# OpenSegment-v10.net
KiCad netlist of a schematic drawn in EAGLE
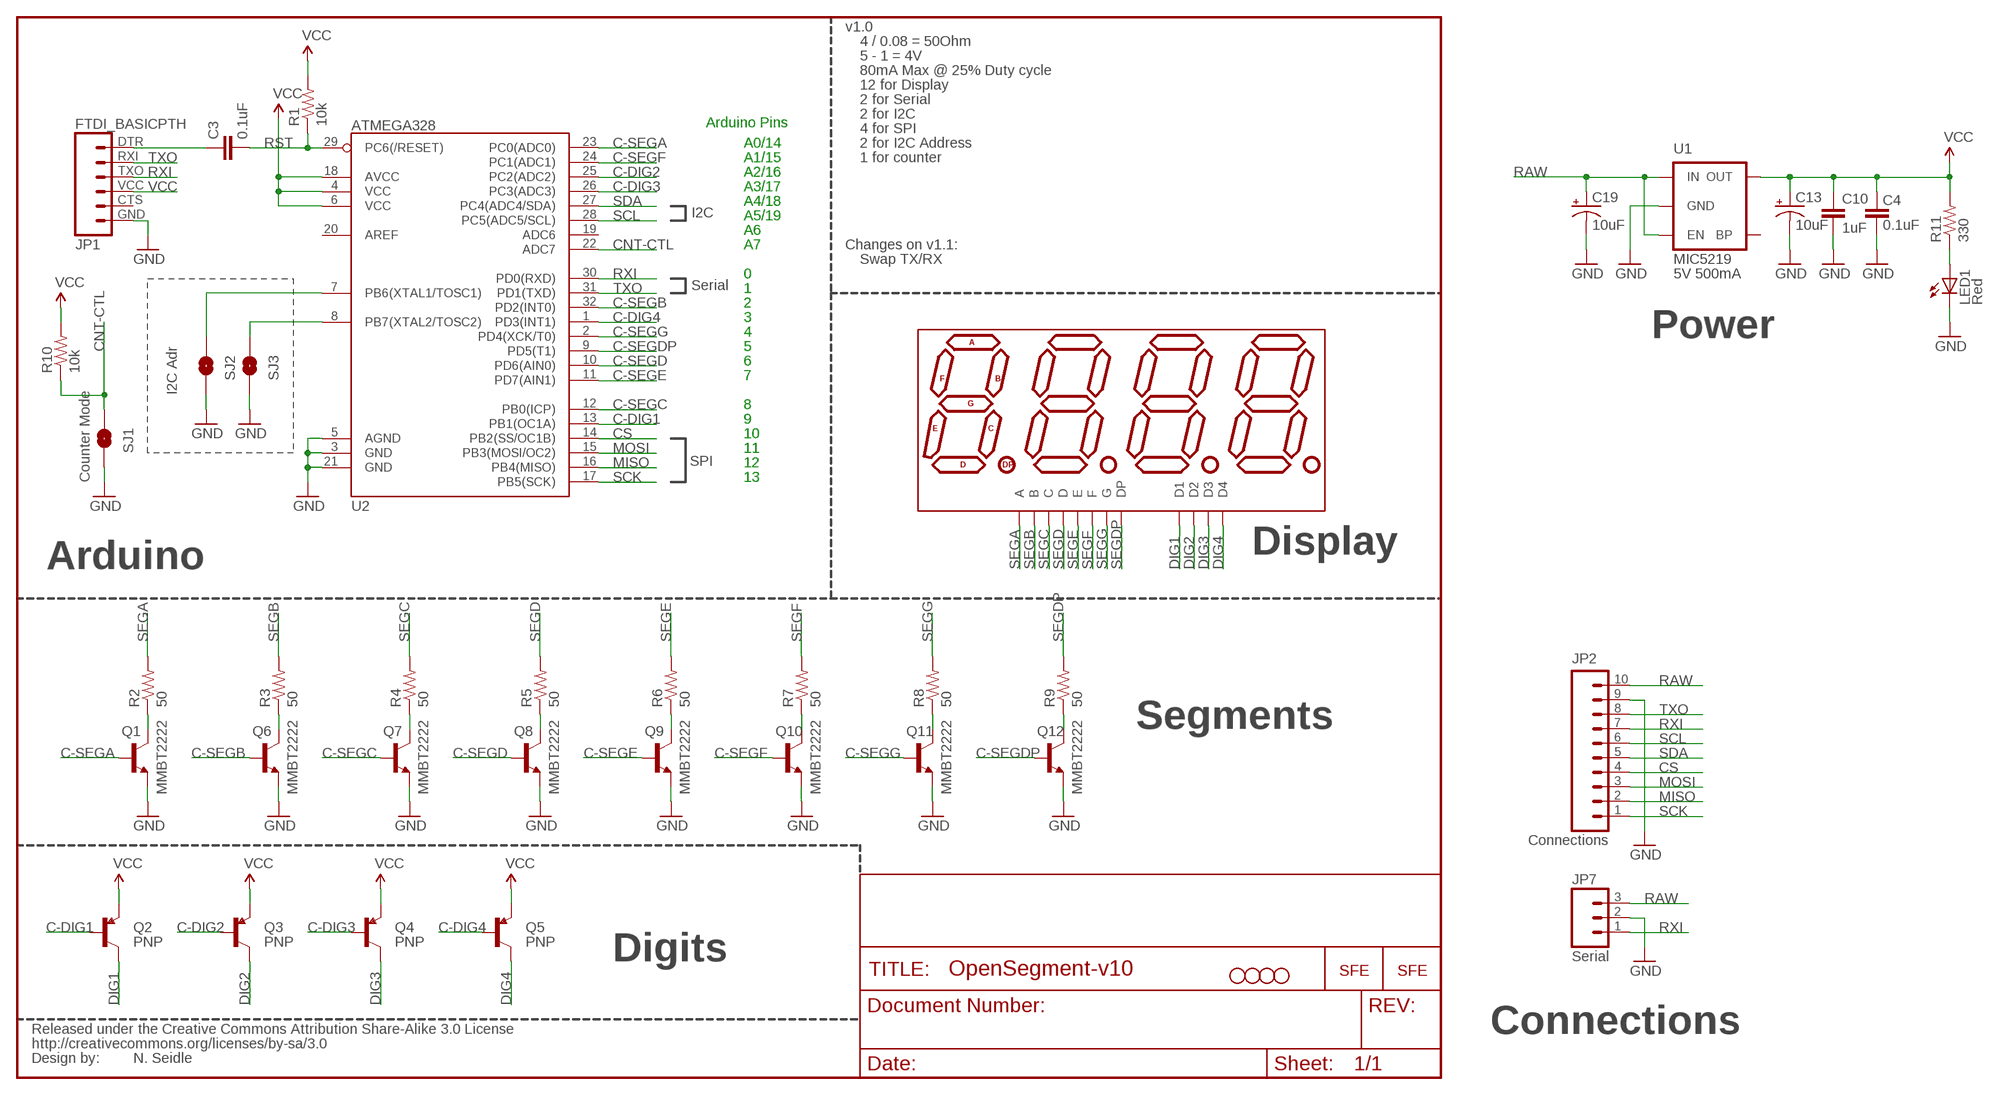
[diagram p0: schematic, sheet 1]

(export (version "E")
  (design (tool "Eeschema 10.0.6"))
  (components
    (comp (ref "C3")
      (value "0.1uF")
      (footprint "eagle-import:0402-CAP")
      (libsource (lib "eagle-import") (part "CAP0402-CAP"))
    )
    (comp (ref "C4")
      (value "0.1uF")
      (footprint "eagle-import:0402-CAP")
      (libsource (lib "eagle-import") (part "CAP0402-CAP"))
    )
    (comp (ref "C10")
      (value "1uF")
      (footprint "eagle-import:0402-CAP")
      (libsource (lib "eagle-import") (part "CAP0402-CAP"))
    )
    (comp (ref "C13")
      (value "10uF")
      (footprint "eagle-import:EIA3216")
      (libsource (lib "eagle-import") (part "CAP_POL1206"))
    )
    (comp (ref "C19")
      (value "10uF")
      (footprint "eagle-import:EIA3216")
      (libsource (lib "eagle-import") (part "CAP_POL1206"))
    )
    (comp (ref "JP1")
      (value "FTDI_BASICPTH")
      (footprint "eagle-import:FTDI_BASIC")
      (libsource (lib "eagle-import") (part "FTDI_BASICPTH"))
    )
    (comp (ref "JP2")
      (value "Connections")
      (footprint "eagle-import:1X10")
      (libsource (lib "eagle-import") (part "M10{dblquote}"))
    )
    (comp (ref "JP3")
      (value "STAND-OFF")
      (footprint "eagle-import:STAND-OFF")
      (libsource (lib "eagle-import") (part "STAND-OFF"))
    )
    (comp (ref "JP4")
      (value "STAND-OFF")
      (footprint "eagle-import:STAND-OFF")
      (libsource (lib "eagle-import") (part "STAND-OFF"))
    )
    (comp (ref "JP5")
      (value "STAND-OFF")
      (footprint "eagle-import:STAND-OFF")
      (libsource (lib "eagle-import") (part "STAND-OFF"))
    )
    (comp (ref "JP6")
      (value "STAND-OFF")
      (footprint "eagle-import:STAND-OFF")
      (libsource (lib "eagle-import") (part "STAND-OFF"))
    )
    (comp (ref "JP7")
      (value "Serial")
      (footprint "eagle-import:JST-3-SMD")
      (libsource (lib "eagle-import") (part "M03"))
    )
    (comp (ref "LED1")
      (value "Red")
      (footprint "eagle-import:LED-0603")
      (libsource (lib "eagle-import") (part "LED0603"))
    )
    (comp (ref "Q1")
      (value "MMBT2222")
      (footprint "eagle-import:SOT23-3")
      (libsource (lib "eagle-import") (part "TRANSISTOR_NPNSOT23-3"))
    )
    (comp (ref "Q2")
      (value "PNP")
      (footprint "eagle-import:SOT23-3")
      (libsource (lib "eagle-import") (part "TRANSISTOR_PNPSMD"))
    )
    (comp (ref "Q3")
      (value "PNP")
      (footprint "eagle-import:SOT23-3")
      (libsource (lib "eagle-import") (part "TRANSISTOR_PNPSMD"))
    )
    (comp (ref "Q4")
      (value "PNP")
      (footprint "eagle-import:SOT23-3")
      (libsource (lib "eagle-import") (part "TRANSISTOR_PNPSMD"))
    )
    (comp (ref "Q5")
      (value "PNP")
      (footprint "eagle-import:SOT23-3")
      (libsource (lib "eagle-import") (part "TRANSISTOR_PNPSMD"))
    )
    (comp (ref "Q6")
      (value "MMBT2222")
      (footprint "eagle-import:SOT23-3")
      (libsource (lib "eagle-import") (part "TRANSISTOR_NPNSOT23-3"))
    )
    (comp (ref "Q7")
      (value "MMBT2222")
      (footprint "eagle-import:SOT23-3")
      (libsource (lib "eagle-import") (part "TRANSISTOR_NPNSOT23-3"))
    )
    (comp (ref "Q8")
      (value "MMBT2222")
      (footprint "eagle-import:SOT23-3")
      (libsource (lib "eagle-import") (part "TRANSISTOR_NPNSOT23-3"))
    )
    (comp (ref "Q9")
      (value "MMBT2222")
      (footprint "eagle-import:SOT23-3")
      (libsource (lib "eagle-import") (part "TRANSISTOR_NPNSOT23-3"))
    )
    (comp (ref "Q10")
      (value "MMBT2222")
      (footprint "eagle-import:SOT23-3")
      (libsource (lib "eagle-import") (part "TRANSISTOR_NPNSOT23-3"))
    )
    (comp (ref "Q11")
      (value "MMBT2222")
      (footprint "eagle-import:SOT23-3")
      (libsource (lib "eagle-import") (part "TRANSISTOR_NPNSOT23-3"))
    )
    (comp (ref "Q12")
      (value "MMBT2222")
      (footprint "eagle-import:SOT23-3")
      (libsource (lib "eagle-import") (part "TRANSISTOR_NPNSOT23-3"))
    )
    (comp (ref "R1")
      (value "10k")
      (footprint "eagle-import:0402-RES")
      (libsource (lib "eagle-import") (part "RESISTOR0402-RES"))
    )
    (comp (ref "R2")
      (value "50")
      (footprint "eagle-import:0402-RES")
      (libsource (lib "eagle-import") (part "RESISTOR0402-RES"))
    )
    (comp (ref "R3")
      (value "50")
      (footprint "eagle-import:0402-RES")
      (libsource (lib "eagle-import") (part "RESISTOR0402-RES"))
    )
    (comp (ref "R4")
      (value "50")
      (footprint "eagle-import:0402-RES")
      (libsource (lib "eagle-import") (part "RESISTOR0402-RES"))
    )
    (comp (ref "R5")
      (value "50")
      (footprint "eagle-import:0402-RES")
      (libsource (lib "eagle-import") (part "RESISTOR0402-RES"))
    )
    (comp (ref "R6")
      (value "50")
      (footprint "eagle-import:0402-RES")
      (libsource (lib "eagle-import") (part "RESISTOR0402-RES"))
    )
    (comp (ref "R7")
      (value "50")
      (footprint "eagle-import:0402-RES")
      (libsource (lib "eagle-import") (part "RESISTOR0402-RES"))
    )
    (comp (ref "R8")
      (value "50")
      (footprint "eagle-import:0402-RES")
      (libsource (lib "eagle-import") (part "RESISTOR0402-RES"))
    )
    (comp (ref "R9")
      (value "50")
      (footprint "eagle-import:0402-RES")
      (libsource (lib "eagle-import") (part "RESISTOR0402-RES"))
    )
    (comp (ref "R10")
      (value "10k")
      (footprint "eagle-import:0402-RES")
      (libsource (lib "eagle-import") (part "RESISTOR0402-RES"))
    )
    (comp (ref "R11")
      (value "330")
      (footprint "eagle-import:0402-RES")
      (libsource (lib "eagle-import") (part "RESISTOR0402-RES"))
    )
    (comp (ref "SJ1")
      (value "Counter Ctl")
      (footprint "eagle-import:SJ_2S-NO")
      (libsource (lib "eagle-import") (part "SOLDERJUMPERNO"))
    )
    (comp (ref "SJ2")
      (value "Counter Ctl")
      (footprint "eagle-import:SJ_2S-NO")
      (libsource (lib "eagle-import") (part "SOLDERJUMPERNO"))
    )
    (comp (ref "SJ3")
      (value "Counter Ctl")
      (footprint "eagle-import:SJ_2S-NO")
      (libsource (lib "eagle-import") (part "SOLDERJUMPERNO"))
    )
    (comp (ref "U$1")
      (value "LOGO-SFESK")
      (footprint "eagle-import:SFE-LOGO-FLAME")
      (libsource (lib "eagle-import") (part "LOGO-SFESK"))
    )
    (comp (ref "U$3")
      (value "CREATIVE_COMMONS")
      (footprint "eagle-import:CREATIVE_COMMONS")
      (libsource (lib "eagle-import") (part "CREATIVE_COMMONS"))
    )
    (comp (ref "U$7")
      (value "LOGO-SFENW2")
      (footprint "eagle-import:SFE-NEW-WEB")
      (libsource (lib "eagle-import") (part "LOGO-SFENW2"))
    )
    (comp (ref "U1")
      (value "MIC5219")
      (footprint "eagle-import:SOT23-5")
      (libsource (lib "eagle-import") (part "V_REG_LDOSMD"))
    )
    (comp (ref "U2")
      (value "ATMEGA328")
      (footprint "eagle-import:TQFP32-08")
      (libsource (lib "eagle-import") (part "ATMEGA168"))
    )
    (comp (ref "U3")
      (value "7-SEGMENT-4DIGIT-COUNTERPTH")
      (footprint "eagle-import:7-SEGMENT-4DIGIT-COUNTER")
      (libsource (lib "eagle-import") (part "7-SEGMENT-4DIGIT-COUNTERPTH"))
    )
  )
  (nets
    (net (code "1") (name "/C-DIG1") (class "Default")
      (node (ref "Q2") (pin "1") (pinfunction "B_1") (pintype "passive"))
      (node (ref "U2") (pin "13") (pinfunction "PB1(OC1A)_13") (pintype "bidirectional"))
    )
    (net (code "2") (name "/C-DIG2") (class "Default")
      (node (ref "Q3") (pin "1") (pinfunction "B_1") (pintype "passive"))
      (node (ref "U2") (pin "25") (pinfunction "PC2(ADC2)_25") (pintype "bidirectional"))
    )
    (net (code "3") (name "/C-DIG3") (class "Default")
      (node (ref "Q4") (pin "1") (pinfunction "B_1") (pintype "passive"))
      (node (ref "U2") (pin "26") (pinfunction "PC3(ADC3)_26") (pintype "bidirectional"))
    )
    (net (code "4") (name "/C-DIG4") (class "Default")
      (node (ref "Q5") (pin "1") (pinfunction "B_1") (pintype "passive"))
      (node (ref "U2") (pin "1") (pinfunction "PD3(INT1)_1") (pintype "bidirectional"))
    )
    (net (code "5") (name "/C-SEGA") (class "Default")
      (node (ref "Q1") (pin "1") (pinfunction "B_1") (pintype "passive"))
      (node (ref "U2") (pin "23") (pinfunction "PC0(ADC0)_23") (pintype "bidirectional"))
    )
    (net (code "6") (name "/C-SEGB") (class "Default")
      (node (ref "Q6") (pin "1") (pinfunction "B_1") (pintype "passive"))
      (node (ref "U2") (pin "32") (pinfunction "PD2(INT0)_32") (pintype "bidirectional"))
    )
    (net (code "7") (name "/C-SEGC") (class "Default")
      (node (ref "Q7") (pin "1") (pinfunction "B_1") (pintype "passive"))
      (node (ref "U2") (pin "12") (pinfunction "PB0(ICP)_12") (pintype "bidirectional"))
    )
    (net (code "8") (name "/C-SEGD") (class "Default")
      (node (ref "Q8") (pin "1") (pinfunction "B_1") (pintype "passive"))
      (node (ref "U2") (pin "10") (pinfunction "PD6(AIN0)_10") (pintype "bidirectional"))
    )
    (net (code "9") (name "/C-SEGDP") (class "Default")
      (node (ref "Q12") (pin "1") (pinfunction "B_1") (pintype "passive"))
      (node (ref "U2") (pin "9") (pinfunction "PD5(T1)_9") (pintype "bidirectional"))
    )
    (net (code "10") (name "/C-SEGE") (class "Default")
      (node (ref "Q9") (pin "1") (pinfunction "B_1") (pintype "passive"))
      (node (ref "U2") (pin "11") (pinfunction "PD7(AIN1)_11") (pintype "bidirectional"))
    )
    (net (code "11") (name "/C-SEGF") (class "Default")
      (node (ref "Q10") (pin "1") (pinfunction "B_1") (pintype "passive"))
      (node (ref "U2") (pin "24") (pinfunction "PC1(ADC1)_24") (pintype "bidirectional"))
    )
    (net (code "12") (name "/C-SEGG") (class "Default")
      (node (ref "Q11") (pin "1") (pinfunction "B_1") (pintype "passive"))
      (node (ref "U2") (pin "2") (pinfunction "PD4(XCK/T0)_2") (pintype "bidirectional"))
    )
    (net (code "13") (name "/CNT-CTL") (class "Default")
      (node (ref "R10") (pin "1") (pinfunction "1_1") (pintype "passive"))
      (node (ref "SJ1") (pin "1") (pinfunction "1_1") (pintype "passive"))
      (node (ref "U2") (pin "22") (pinfunction "ADC7_22") (pintype "bidirectional"))
    )
    (net (code "14") (name "/CS") (class "Default")
      (node (ref "JP2") (pin "4") (pinfunction "4_4") (pintype "passive"))
      (node (ref "U2") (pin "14") (pinfunction "PB2(SS/OC1B)_14") (pintype "bidirectional"))
    )
    (net (code "15") (name "/DIG1") (class "Default")
      (node (ref "Q2") (pin "3") (pinfunction "C_3") (pintype "passive"))
      (node (ref "U3") (pin "12") (pinfunction "D1_12") (pintype "bidirectional"))
    )
    (net (code "16") (name "/DIG2") (class "Default")
      (node (ref "Q3") (pin "3") (pinfunction "C_3") (pintype "passive"))
      (node (ref "U3") (pin "9") (pinfunction "D2_9") (pintype "bidirectional"))
    )
    (net (code "17") (name "/DIG3") (class "Default")
      (node (ref "Q4") (pin "3") (pinfunction "C_3") (pintype "passive"))
      (node (ref "U3") (pin "8") (pinfunction "D3_8") (pintype "bidirectional"))
    )
    (net (code "18") (name "/DIG4") (class "Default")
      (node (ref "Q5") (pin "3") (pinfunction "C_3") (pintype "passive"))
      (node (ref "U3") (pin "6") (pinfunction "D4_6") (pintype "bidirectional"))
    )
    (net (code "19") (name "/MISO") (class "Default")
      (node (ref "JP2") (pin "2") (pinfunction "2_2") (pintype "passive"))
      (node (ref "U2") (pin "16") (pinfunction "PB4(MISO)_16") (pintype "bidirectional"))
    )
    (net (code "20") (name "/MOSI") (class "Default")
      (node (ref "JP2") (pin "3") (pinfunction "3_3") (pintype "passive"))
      (node (ref "U2") (pin "15") (pinfunction "PB3(MOSI/OC2)_15") (pintype "bidirectional"))
    )
    (net (code "21") (name "/RAW") (class "Default")
      (node (ref "C19") (pin "A") (pinfunction "+_A") (pintype "passive"))
      (node (ref "JP2") (pin "10") (pinfunction "10_10") (pintype "passive"))
      (node (ref "JP7") (pin "3") (pinfunction "3_3") (pintype "passive"))
      (node (ref "U1") (pin "1") (pinfunction "IN_1") (pintype "input"))
      (node (ref "U1") (pin "3") (pinfunction "EN_3") (pintype "input"))
    )
    (net (code "22") (name "/RST") (class "Default")
      (node (ref "C3") (pin "2") (pinfunction "2_2") (pintype "passive"))
      (node (ref "R1") (pin "1") (pinfunction "1_1") (pintype "passive"))
      (node (ref "U2") (pin "29") (pinfunction "PC6(/RESET)_29") (pintype "bidirectional"))
    )
    (net (code "23") (name "/RXI") (class "Default")
      (node (ref "JP1") (pin "TXO") (pinfunction "3_TXO") (pintype "passive"))
      (node (ref "JP2") (pin "7") (pinfunction "7_7") (pintype "passive"))
      (node (ref "JP7") (pin "1") (pinfunction "1_1") (pintype "passive"))
      (node (ref "U2") (pin "30") (pinfunction "PD0(RXD)_30") (pintype "bidirectional"))
    )
    (net (code "24") (name "/SCK") (class "Default")
      (node (ref "JP2") (pin "1") (pinfunction "1_1") (pintype "passive"))
      (node (ref "U2") (pin "17") (pinfunction "PB5(SCK)_17") (pintype "bidirectional"))
    )
    (net (code "25") (name "/SCL") (class "Default")
      (node (ref "JP2") (pin "6") (pinfunction "6_6") (pintype "passive"))
      (node (ref "U2") (pin "28") (pinfunction "PC5(ADC5/SCL)_28") (pintype "bidirectional"))
    )
    (net (code "26") (name "/SDA") (class "Default")
      (node (ref "JP2") (pin "5") (pinfunction "5_5") (pintype "passive"))
      (node (ref "U2") (pin "27") (pinfunction "PC4(ADC4/SDA)_27") (pintype "bidirectional"))
    )
    (net (code "27") (name "/SEGA") (class "Default")
      (node (ref "R2") (pin "2") (pinfunction "2_2") (pintype "passive"))
      (node (ref "U3") (pin "11") (pinfunction "A_11") (pintype "bidirectional"))
    )
    (net (code "28") (name "/SEGB") (class "Default")
      (node (ref "R3") (pin "2") (pinfunction "2_2") (pintype "passive"))
      (node (ref "U3") (pin "7") (pinfunction "B_7") (pintype "bidirectional"))
    )
    (net (code "29") (name "/SEGC") (class "Default")
      (node (ref "R4") (pin "2") (pinfunction "2_2") (pintype "passive"))
      (node (ref "U3") (pin "4") (pinfunction "C_4") (pintype "bidirectional"))
    )
    (net (code "30") (name "/SEGD") (class "Default")
      (node (ref "R5") (pin "2") (pinfunction "2_2") (pintype "passive"))
      (node (ref "U3") (pin "2") (pinfunction "D_2") (pintype "bidirectional"))
    )
    (net (code "31") (name "/SEGDP") (class "Default")
      (node (ref "R9") (pin "2") (pinfunction "2_2") (pintype "passive"))
      (node (ref "U3") (pin "3") (pinfunction "DP_3") (pintype "bidirectional"))
    )
    (net (code "32") (name "/SEGE") (class "Default")
      (node (ref "R6") (pin "2") (pinfunction "2_2") (pintype "passive"))
      (node (ref "U3") (pin "1") (pinfunction "E_1") (pintype "bidirectional"))
    )
    (net (code "33") (name "/SEGF") (class "Default")
      (node (ref "R7") (pin "2") (pinfunction "2_2") (pintype "passive"))
      (node (ref "U3") (pin "10") (pinfunction "F_10") (pintype "bidirectional"))
    )
    (net (code "34") (name "/SEGG") (class "Default")
      (node (ref "R8") (pin "2") (pinfunction "2_2") (pintype "passive"))
      (node (ref "U3") (pin "5") (pinfunction "G_5") (pintype "bidirectional"))
    )
    (net (code "35") (name "/TXO") (class "Default")
      (node (ref "JP1") (pin "RXI") (pinfunction "2_RXI") (pintype "passive"))
      (node (ref "JP2") (pin "8") (pinfunction "8_8") (pintype "passive"))
      (node (ref "U2") (pin "31") (pinfunction "PD1(TXD)_31") (pintype "bidirectional"))
    )
    (net (code "36") (name "GND") (class "Default")
      (node (ref "C10") (pin "2") (pinfunction "2_2") (pintype "passive"))
      (node (ref "C13") (pin "C") (pinfunction "-_C") (pintype "passive"))
      (node (ref "C19") (pin "C") (pinfunction "-_C") (pintype "passive"))
      (node (ref "C4") (pin "1") (pinfunction "1_1") (pintype "passive"))
      (node (ref "JP1") (pin "GND") (pinfunction "6_GND") (pintype "passive"))
      (node (ref "JP2") (pin "9") (pinfunction "9_9") (pintype "passive"))
      (node (ref "JP7") (pin "2") (pinfunction "2_2") (pintype "passive"))
      (node (ref "LED1") (pin "C") (pinfunction "C_C") (pintype "passive"))
      (node (ref "Q1") (pin "2") (pinfunction "E_2") (pintype "passive"))
      (node (ref "Q10") (pin "2") (pinfunction "E_2") (pintype "passive"))
      (node (ref "Q11") (pin "2") (pinfunction "E_2") (pintype "passive"))
      (node (ref "Q12") (pin "2") (pinfunction "E_2") (pintype "passive"))
      (node (ref "Q6") (pin "2") (pinfunction "E_2") (pintype "passive"))
      (node (ref "Q7") (pin "2") (pinfunction "E_2") (pintype "passive"))
      (node (ref "Q8") (pin "2") (pinfunction "E_2") (pintype "passive"))
      (node (ref "Q9") (pin "2") (pinfunction "E_2") (pintype "passive"))
      (node (ref "SJ1") (pin "2") (pinfunction "2_2") (pintype "passive"))
      (node (ref "SJ2") (pin "2") (pinfunction "2_2") (pintype "passive"))
      (node (ref "SJ3") (pin "2") (pinfunction "2_2") (pintype "passive"))
      (node (ref "U1") (pin "2") (pinfunction "GND_2") (pintype "input"))
      (node (ref "U2") (pin "21") (pinfunction "GND_21") (pintype "bidirectional"))
      (node (ref "U2") (pin "3") (pinfunction "GND_3") (pintype "bidirectional"))
      (node (ref "U2") (pin "5") (pinfunction "AGND_5") (pintype "bidirectional"))
    )
    (net (code "37") (name "Net-(JP1-1)") (class "Default")
      (node (ref "C3") (pin "1") (pinfunction "1_1") (pintype "passive"))
      (node (ref "JP1") (pin "DTR") (pinfunction "1_DTR") (pintype "passive"))
    )
    (net (code "38") (name "Net-(LED1-PadA)") (class "Default")
      (node (ref "LED1") (pin "A") (pinfunction "A_A") (pintype "passive"))
      (node (ref "R11") (pin "1") (pinfunction "1_1") (pintype "passive"))
    )
    (net (code "39") (name "Net-(Q1-C)") (class "Default")
      (node (ref "Q1") (pin "3") (pinfunction "C_3") (pintype "passive"))
      (node (ref "R2") (pin "1") (pinfunction "1_1") (pintype "passive"))
    )
    (net (code "40") (name "Net-(Q6-C)") (class "Default")
      (node (ref "Q6") (pin "3") (pinfunction "C_3") (pintype "passive"))
      (node (ref "R3") (pin "1") (pinfunction "1_1") (pintype "passive"))
    )
    (net (code "41") (name "Net-(Q7-C)") (class "Default")
      (node (ref "Q7") (pin "3") (pinfunction "C_3") (pintype "passive"))
      (node (ref "R4") (pin "1") (pinfunction "1_1") (pintype "passive"))
    )
    (net (code "42") (name "Net-(Q8-C)") (class "Default")
      (node (ref "Q8") (pin "3") (pinfunction "C_3") (pintype "passive"))
      (node (ref "R5") (pin "1") (pinfunction "1_1") (pintype "passive"))
    )
    (net (code "43") (name "Net-(Q9-C)") (class "Default")
      (node (ref "Q9") (pin "3") (pinfunction "C_3") (pintype "passive"))
      (node (ref "R6") (pin "1") (pinfunction "1_1") (pintype "passive"))
    )
    (net (code "44") (name "Net-(Q10-C)") (class "Default")
      (node (ref "Q10") (pin "3") (pinfunction "C_3") (pintype "passive"))
      (node (ref "R7") (pin "1") (pinfunction "1_1") (pintype "passive"))
    )
    (net (code "45") (name "Net-(Q11-C)") (class "Default")
      (node (ref "Q11") (pin "3") (pinfunction "C_3") (pintype "passive"))
      (node (ref "R8") (pin "1") (pinfunction "1_1") (pintype "passive"))
    )
    (net (code "46") (name "Net-(Q12-C)") (class "Default")
      (node (ref "Q12") (pin "3") (pinfunction "C_3") (pintype "passive"))
      (node (ref "R9") (pin "1") (pinfunction "1_1") (pintype "passive"))
    )
    (net (code "47") (name "Net-(U2-PB6(XTAL1{slash}TOSC1))") (class "Default")
      (node (ref "SJ2") (pin "1") (pinfunction "1_1") (pintype "passive"))
      (node (ref "U2") (pin "7") (pinfunction "PB6(XTAL1/TOSC1)_7") (pintype "bidirectional"))
    )
    (net (code "48") (name "Net-(U2-PB7(XTAL2{slash}TOSC2))") (class "Default")
      (node (ref "SJ3") (pin "1") (pinfunction "1_1") (pintype "passive"))
      (node (ref "U2") (pin "8") (pinfunction "PB7(XTAL2/TOSC2)_8") (pintype "bidirectional"))
    )
    (net (code "49") (name "VCC") (class "Default")
      (node (ref "C10") (pin "1") (pinfunction "1_1") (pintype "passive"))
      (node (ref "C13") (pin "A") (pinfunction "+_A") (pintype "passive"))
      (node (ref "C4") (pin "2") (pinfunction "2_2") (pintype "passive"))
      (node (ref "JP1") (pin "VCC") (pinfunction "4_VCC") (pintype "passive"))
      (node (ref "Q2") (pin "2") (pinfunction "E_2") (pintype "passive"))
      (node (ref "Q3") (pin "2") (pinfunction "E_2") (pintype "passive"))
      (node (ref "Q4") (pin "2") (pinfunction "E_2") (pintype "passive"))
      (node (ref "Q5") (pin "2") (pinfunction "E_2") (pintype "passive"))
      (node (ref "R1") (pin "2") (pinfunction "2_2") (pintype "passive"))
      (node (ref "R10") (pin "2") (pinfunction "2_2") (pintype "passive"))
      (node (ref "R11") (pin "2") (pinfunction "2_2") (pintype "passive"))
      (node (ref "U1") (pin "5") (pinfunction "OUT_5") (pintype "passive"))
      (node (ref "U2") (pin "18") (pinfunction "AVCC_18") (pintype "bidirectional"))
      (node (ref "U2") (pin "4") (pinfunction "VCC_4") (pintype "bidirectional"))
      (node (ref "U2") (pin "6") (pinfunction "VCC_6") (pintype "bidirectional"))
    )
    (net (code "50") (name "unconnected-(JP1-5-PadCTS)") (class "Default")
      (node (ref "JP1") (pin "CTS") (pinfunction "5_CTS") (pintype "passive"))
    )
    (net (code "51") (name "unconnected-(U1-BP-Pad4)") (class "Default")
      (node (ref "U1") (pin "4") (pinfunction "BP_4") (pintype "input"))
    )
    (net (code "52") (name "unconnected-(U2-ADC6-Pad19)") (class "Default")
      (node (ref "U2") (pin "19") (pinfunction "ADC6_19") (pintype "bidirectional"))
    )
    (net (code "53") (name "unconnected-(U2-AREF-Pad20)") (class "Default")
      (node (ref "U2") (pin "20") (pinfunction "AREF_20") (pintype "bidirectional"))
    )
  )
)
